# Sitara_IO_Bank_6.net
KiCad netlist of a schematic drawn in Altium Designer
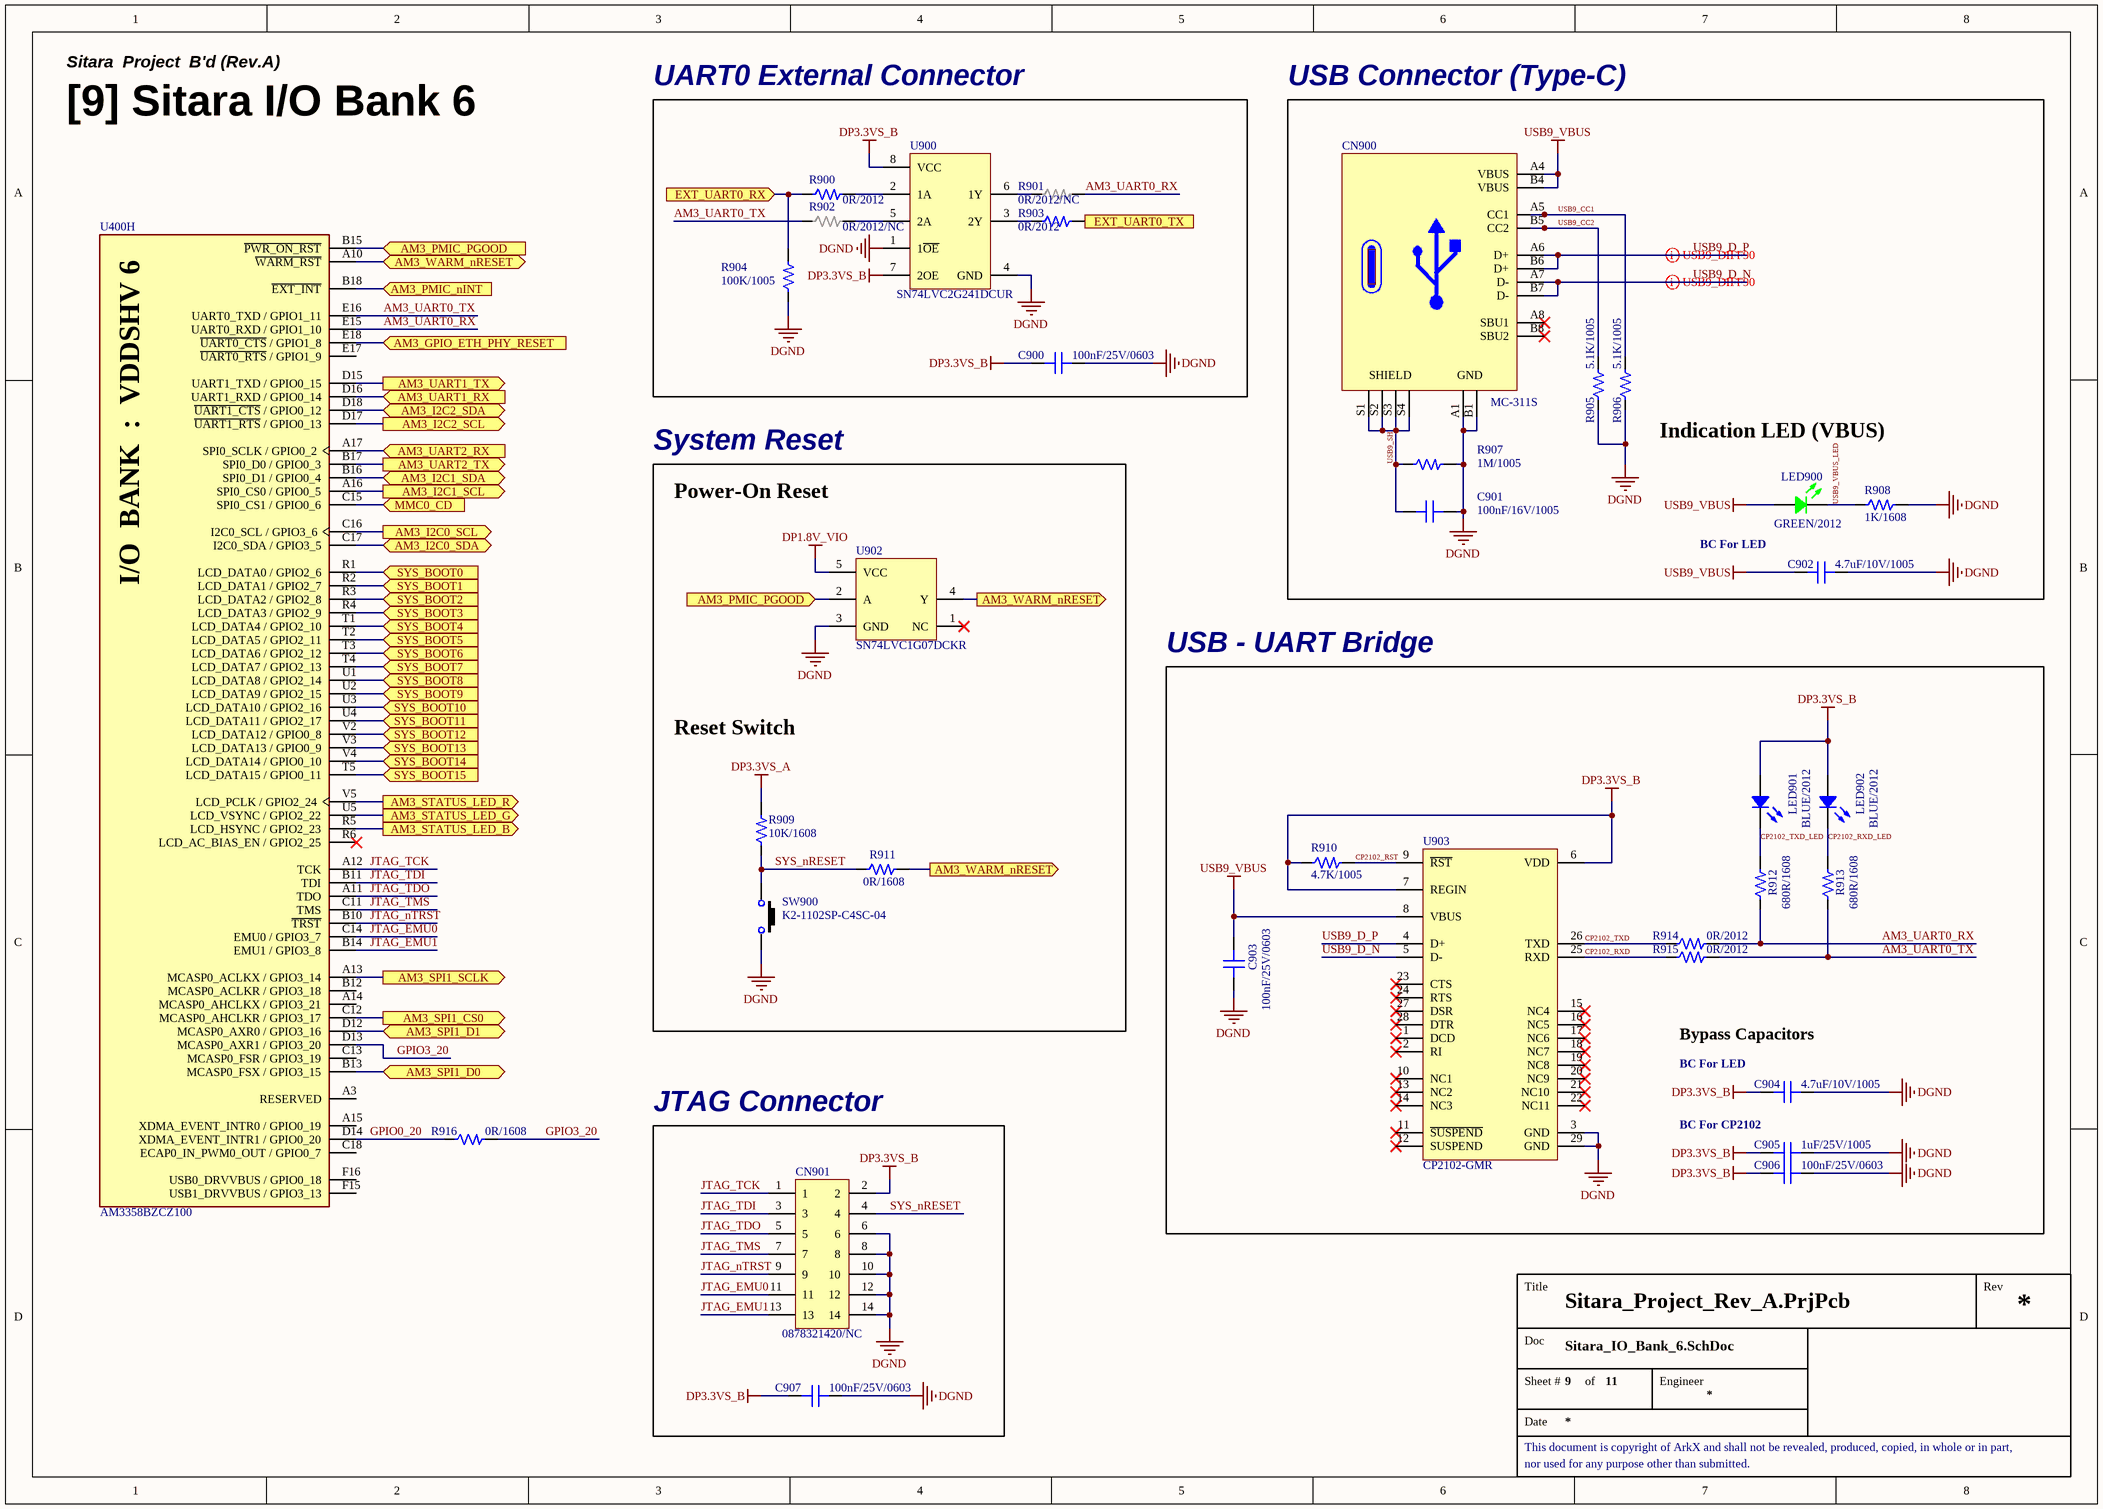
[diagram p0: Sitara_IO_Bank_6.SchDoc]

(export (version "E")
  (design (tool "Eeschema 10.0.6"))
  (components
    (comp (ref "C900")
      (value "100nF/25V/0603")
      (footprint "CAP 0603 (0201_INCH)")
      (description "Ceramic CAP_100nF/25V/0603")
      (fields (field (name "LCSC PART #") "C181047"))
      (libsource (lib "Arkx") (part "CAP_100nF/25V/0603"))
    )
    (comp (ref "C901")
      (value "100nF/16V/1005")
      (footprint "CAP 1005 (0402_INCH)")
      (description "Ceramic CAP_100nF/16V/1005")
      (fields (field (name "LCSC PART #") "C1525"))
      (libsource (lib "Arkx") (part "CAP_100nF/16V/1005"))
    )
    (comp (ref "C902")
      (value "4.7uF/10V/1005")
      (footprint "CAP 1005 (0402_INCH)")
      (description "10V 4.7uF X5R ±20% 0402  Multilayer Ceramic Capacitors MLCC - SMD/SMT ROHS")
      (fields (field (name "LCSC PART #") "C23733"))
      (libsource (lib "Arkx") (part "CAP_4.7uF/10V/1005"))
    )
    (comp (ref "C903")
      (value "100nF/25V/0603")
      (footprint "CAP 0603 (0201_INCH)")
      (description "Ceramic CAP_100nF/25V/0603")
      (fields (field (name "LCSC PART #") "C181047"))
      (libsource (lib "Arkx") (part "CAP_100nF/25V/0603"))
    )
    (comp (ref "C904")
      (value "4.7uF/10V/1005")
      (footprint "CAP 1005 (0402_INCH)")
      (description "10V 4.7uF X5R ±20% 0402  Multilayer Ceramic Capacitors MLCC - SMD/SMT ROHS")
      (fields (field (name "LCSC PART #") "C23733"))
      (libsource (lib "Arkx") (part "CAP_4.7uF/10V/1005"))
    )
    (comp (ref "C905")
      (value "1uF/25V/1005")
      (footprint "CAP 1005 (0402_INCH)")
      (description "Ceramic CAP_1uF/25V/1005")
      (fields (field (name "LCSC PART #") "C52923"))
      (libsource (lib "Arkx") (part "CAP_1uF/25V/1005"))
    )
    (comp (ref "C906")
      (value "100nF/25V/0603")
      (footprint "CAP 0603 (0201_INCH)")
      (description "Ceramic CAP_100nF/25V/0603")
      (fields (field (name "LCSC PART #") "C181047"))
      (libsource (lib "Arkx") (part "CAP_100nF/25V/0603"))
    )
    (comp (ref "C907")
      (value "100nF/25V/0603")
      (footprint "CAP 0603 (0201_INCH)")
      (description "Ceramic CAP_100nF/25V/0603")
      (fields (field (name "LCSC PART #") "C181047"))
      (libsource (lib "Arkx") (part "CAP_100nF/25V/0603"))
    )
    (comp (ref "CN900")
      (value "MC-311S")
      (footprint "CON USB-Type-C (16P)")
      (description "USB 2.0 5A 1 Surface Mount 16 Female -35℃~+75℃ Type-C SMD  USB Connectors ROHS")
      (fields (field (name "LCSC PART #") "C2977718"))
      (libsource (lib "Arkx") (part "CON_USB-Type-C"))
    )
    (comp (ref "CN901")
      (value "0878321420/NC")
      (footprint "CON_NC_BOX_HEADER_DUAL_2x7PIN(2.00MM) (0878321420)")
      (description "CONN HEADER SMD 14POS 2MM")
      (libsource (lib "Arkx") (part "CON_NC_BOX_HEADER_DUAL_2x7PIN(2.00MM)_1"))
    )
    (comp (ref "LED900")
      (value "GREEN/2012")
      (footprint "LED MHT170RGBCT (GREEN)")
      (fields (field (name "LCSC PART #") "C2962094"))
      (libsource (lib "Arkx") (part "LED_MHT170RGBCT(GREEN)"))
    )
    (comp (ref "LED901")
      (value "BLUE/2012")
      (footprint "LED MHT170RGBCT (BLUE)")
      (fields (field (name "LCSC PART #") "C2962094"))
      (libsource (lib "Arkx") (part "LED_MHT170RGBCT(BLUE)"))
    )
    (comp (ref "LED902")
      (value "BLUE/2012")
      (footprint "LED MHT170RGBCT (BLUE)")
      (fields (field (name "LCSC PART #") "C2962094"))
      (libsource (lib "Arkx") (part "LED_MHT170RGBCT(BLUE)"))
    )
    (comp (ref "R900")
      (value "0R/2012")
      (footprint "RES 2012 (0805_inch)")
      (description "RES_0R/2012/0.125W")
      (fields (field (name "LCSC PART #") "C17477"))
      (libsource (lib "Arkx") (part "RES_0R/2012/0.125W"))
    )
    (comp (ref "R901")
      (value "0R/2012/NC")
      (footprint "RES 2012 (0805_INCH)/NC")
      (description "0R/2012/0.125W/NC")
      (libsource (lib "Arkx") (part "RES_NC_0R/2012/0.125W"))
    )
    (comp (ref "R902")
      (value "0R/2012/NC")
      (footprint "RES 2012 (0805_INCH)/NC")
      (description "0R/2012/0.125W/NC")
      (libsource (lib "Arkx") (part "RES_NC_0R/2012/0.125W"))
    )
    (comp (ref "R903")
      (value "0R/2012")
      (footprint "RES 2012 (0805_inch)")
      (description "RES_0R/2012/0.125W")
      (fields (field (name "LCSC PART #") "C17477"))
      (libsource (lib "Arkx") (part "RES_0R/2012/0.125W"))
    )
    (comp (ref "R904")
      (value "100K/1005")
      (footprint "RES 1005 (0402_inch)")
      (description "RES_100K/1005/62.5mW")
      (fields (field (name "LCSC PART #") "C25741"))
      (libsource (lib "Arkx") (part "RES_100K/1005/62.5mW"))
    )
    (comp (ref "R905")
      (value "5.1K/1005")
      (footprint "RES 1005 (0402_inch)")
      (description "RES_5.1K/1005/62.5mW")
      (fields (field (name "LCSC PART #") "C25905"))
      (libsource (lib "Arkx") (part "RES_5.1K/1005/62.5mW"))
    )
    (comp (ref "R906")
      (value "5.1K/1005")
      (footprint "RES 1005 (0402_inch)")
      (description "RES_5.1K/1005/62.5mW")
      (fields (field (name "LCSC PART #") "C25905"))
      (libsource (lib "Arkx") (part "RES_5.1K/1005/62.5mW"))
    )
    (comp (ref "R907")
      (value "1M/1005")
      (footprint "RES 1005 (0402_inch)")
      (description "RES_1M/1005/62.5mW")
      (fields (field (name "LCSC PART #") "C26083"))
      (libsource (lib "Arkx") (part "RES_1M/1005/62.5mW"))
    )
    (comp (ref "R908")
      (value "1K/1608")
      (footprint "RES 1608 (0603_inch)")
      (description "RES_1K/1608/0.1W")
      (fields (field (name "LCSC PART #") "C21190"))
      (libsource (lib "Arkx") (part "RES_1K/1608/0.1W"))
    )
    (comp (ref "R909")
      (value "10K/1608")
      (footprint "RES 1608 (0603_inch)")
      (description "RES_10K/1608/0.1W")
      (fields (field (name "LCSC PART #") "C25804"))
      (libsource (lib "Arkx") (part "RES_10K/1608/0.1W"))
    )
    (comp (ref "R910")
      (value "4.7K/1005")
      (footprint "RES 1005 (0402_inch)")
      (description "RES_4.7K/1005/62.5mW")
      (fields (field (name "LCSC PART #") "C25900"))
      (libsource (lib "Arkx") (part "RES_4.7K/1005/62.5mW"))
    )
    (comp (ref "R911")
      (value "0R/1608")
      (footprint "RES 1608 (0603_inch)")
      (description "RES_0R/1608/0.1W")
      (fields (field (name "LCSC PART #") "C21189"))
      (libsource (lib "Arkx") (part "RES_0R/1608/0.1W"))
    )
    (comp (ref "R912")
      (value "680R/1608")
      (footprint "RES 1608 (0603_inch)")
      (description "RES_680R/1608/0.1W")
      (fields (field (name "LCSC PART #") "C23228"))
      (libsource (lib "Arkx") (part "RES_680R/1608/0.1W"))
    )
    (comp (ref "R913")
      (value "680R/1608")
      (footprint "RES 1608 (0603_inch)")
      (description "RES_680R/1608/0.1W")
      (fields (field (name "LCSC PART #") "C23228"))
      (libsource (lib "Arkx") (part "RES_680R/1608/0.1W"))
    )
    (comp (ref "R914")
      (value "0R/2012")
      (footprint "RES 2012 (0805_inch)")
      (description "RES_0R/2012/0.125W")
      (fields (field (name "LCSC PART #") "C17477"))
      (libsource (lib "Arkx") (part "RES_0R/2012/0.125W"))
    )
    (comp (ref "R915")
      (value "0R/2012")
      (footprint "RES 2012 (0805_inch)")
      (description "RES_0R/2012/0.125W")
      (fields (field (name "LCSC PART #") "C17477"))
      (libsource (lib "Arkx") (part "RES_0R/2012/0.125W"))
    )
    (comp (ref "R916")
      (value "0R/1608")
      (footprint "RES 1608 (0603_inch)")
      (description "RES_0R/1608/0.1W")
      (fields (field (name "LCSC PART #") "C21189"))
      (libsource (lib "Arkx") (part "RES_0R/1608/0.1W"))
    )
    (comp (ref "SW900")
      (value "K2-1102SP-C4SC-04")
      (footprint "SW K2-1102SP-C4SC-04")
      (fields (field (name "LCSC PART #") "C127509"))
      (libsource (lib "Arkx") (part "SW_K2-1102SP-C4SC-04(2P)"))
    )
    (comp (ref "U400")
      (value "AM3358BZCZ100")
      (footprint "IC_SOC_AM3358BZCZ100")
      (description "ARM® Cortex®-A8 Microprocessor IC Sitara™ 1 Core, 32-Bit 1.0GHz 324-NFBGA (15x15)")
      (fields (field (name "LCSC PART #") "C73932"))
      (libsource (lib "Arkx") (part "IC_SOC_AM3358BZCZ100"))
    )
    (comp (ref "U900")
      (value "SN74LVC2G241DCUR")
      (footprint "IC_VSSOP-8")
      (description "Buffer, Non-Inverting 2 Element 1 Bit per Element 3-State Output 8-VSSOP")
      (fields (field (name "LCSC PART #") "C10430"))
      (libsource (lib "Arkx") (part "IC_BUF_SN74LVC2G241DCUR"))
    )
    (comp (ref "U902")
      (value "SN74LVC1G07DCKR")
      (footprint "IC_SC-70-5")
      (description "Buffer, Non-Inverting 1 Element 1 Bit per Element Open Drain Output SC-70-5")
      (fields (field (name "LCSC PART #") "C7830"))
      (libsource (lib "Arkx") (part "IC_BUF_SN74LVC1G07DCKR"))
    )
    (comp (ref "U903")
      (value "CP2102-GMR")
      (footprint "QFN-28 (5x5mm)")
      (description "Transceiver 1Mbps USB 1/1 QFN-28_5x5x05P  USB ICs ROHS")
      (fields (field (name "LCSC PART #") "C6568"))
      (libsource (lib "Arkx") (part "IC_USB_CP2102"))
    )
  )
  (nets
    (net (code "1") (name "/AM3_GPIO_ETH_PHY_RESET") (class "Default")
      (node (ref "U400") (pin "E18") (pinfunction "~{UART0_CTS}_/_GPIO1_8_E18") (pintype "passive"))
    )
    (net (code "2") (name "/AM3_I2C0_SCL") (class "Default")
      (node (ref "U400") (pin "C16") (pinfunction "I2C0_SCL_/_GPIO3_6_C16") (pintype "passive"))
    )
    (net (code "3") (name "/AM3_I2C0_SDA") (class "Default")
      (node (ref "U400") (pin "C17") (pinfunction "I2C0_SDA_/_GPIO3_5_C17") (pintype "passive"))
    )
    (net (code "4") (name "/AM3_I2C1_SCL") (class "Default")
      (node (ref "U400") (pin "A16") (pinfunction "SPI0_CS0_/_GPIO0_5_A16") (pintype "passive"))
    )
    (net (code "5") (name "/AM3_I2C1_SDA") (class "Default")
      (node (ref "U400") (pin "B16") (pinfunction "SPI0_D1_/_GPIO0_4_B16") (pintype "passive"))
    )
    (net (code "6") (name "/AM3_I2C2_SCL") (class "Default")
      (node (ref "U400") (pin "D17") (pinfunction "~{UART1_RTS}_/_GPIO0_13_D17") (pintype "passive"))
    )
    (net (code "7") (name "/AM3_I2C2_SDA") (class "Default")
      (node (ref "U400") (pin "D18") (pinfunction "~{UART1_CTS}_/_GPIO0_12_D18") (pintype "passive"))
    )
    (net (code "8") (name "/AM3_PMIC_PGOOD") (class "Default")
      (node (ref "U400") (pin "B15") (pinfunction "~{PWR_ON_RST}_B15") (pintype "passive"))
      (node (ref "U902") (pin "2") (pinfunction "A_2") (pintype "passive"))
    )
    (net (code "9") (name "/AM3_PMIC_nINT") (class "Default")
      (node (ref "U400") (pin "B18") (pinfunction "~{EXT_INT}_B18") (pintype "passive"))
    )
    (net (code "10") (name "/AM3_SPI1_CS0") (class "Default")
      (node (ref "U400") (pin "C12") (pinfunction "MCASP0_AHCLKR_/_GPIO3_17_C12") (pintype "passive"))
    )
    (net (code "11") (name "/AM3_SPI1_D0") (class "Default")
      (node (ref "U400") (pin "B13") (pinfunction "MCASP0_FSX_/_GPIO3_15_B13") (pintype "passive"))
    )
    (net (code "12") (name "/AM3_SPI1_D1") (class "Default")
      (node (ref "U400") (pin "D12") (pinfunction "MCASP0_AXR0_/_GPIO3_16_D12") (pintype "passive"))
    )
    (net (code "13") (name "/AM3_SPI1_SCLK") (class "Default")
      (node (ref "U400") (pin "A13") (pinfunction "MCASP0_ACLKX_/_GPIO3_14_A13") (pintype "passive"))
    )
    (net (code "14") (name "/AM3_STATUS_LED_B") (class "Default")
      (node (ref "U400") (pin "R5") (pinfunction "LCD_HSYNC_/_GPIO2_23_R5") (pintype "passive"))
    )
    (net (code "15") (name "/AM3_STATUS_LED_G") (class "Default")
      (node (ref "U400") (pin "U5") (pinfunction "LCD_VSYNC_/_GPIO2_22_U5") (pintype "passive"))
    )
    (net (code "16") (name "/AM3_STATUS_LED_R") (class "Default")
      (node (ref "U400") (pin "V5") (pinfunction "LCD_PCLK_/_GPIO2_24_V5") (pintype "passive"))
    )
    (net (code "17") (name "/AM3_UART0_RX") (class "Default")
      (node (ref "R901") (pin "2") (pinfunction "2_2") (pintype "passive"))
      (node (ref "R912") (pin "1") (pinfunction "1_1") (pintype "passive"))
      (node (ref "R914") (pin "2") (pinfunction "2_2") (pintype "passive"))
      (node (ref "U400") (pin "E15") (pinfunction "UART0_RXD_/_GPIO1_10_E15") (pintype "passive"))
    )
    (net (code "18") (name "/AM3_UART0_TX") (class "Default")
      (node (ref "R902") (pin "1") (pinfunction "1_1") (pintype "passive"))
      (node (ref "R913") (pin "1") (pinfunction "1_1") (pintype "passive"))
      (node (ref "R915") (pin "2") (pinfunction "2_2") (pintype "passive"))
      (node (ref "U400") (pin "E16") (pinfunction "UART0_TXD_/_GPIO1_11_E16") (pintype "passive"))
    )
    (net (code "19") (name "/AM3_UART1_RX") (class "Default")
      (node (ref "U400") (pin "D16") (pinfunction "UART1_RXD_/_GPIO0_14_D16") (pintype "passive"))
    )
    (net (code "20") (name "/AM3_UART1_TX") (class "Default")
      (node (ref "U400") (pin "D15") (pinfunction "UART1_TXD_/_GPIO0_15_D15") (pintype "passive"))
    )
    (net (code "21") (name "/AM3_UART2_RX") (class "Default")
      (node (ref "U400") (pin "A17") (pinfunction "SPI0_SCLK_/_GPIO0_2_A17") (pintype "passive"))
    )
    (net (code "22") (name "/AM3_UART2_TX") (class "Default")
      (node (ref "U400") (pin "B17") (pinfunction "SPI0_D0_/_GPIO0_3_B17") (pintype "passive"))
    )
    (net (code "23") (name "/AM3_WARM_nRESET") (class "Default")
      (node (ref "R911") (pin "2") (pinfunction "2_2") (pintype "passive"))
      (node (ref "U400") (pin "A10") (pinfunction "~{WARM_RST}_A10") (pintype "passive"))
      (node (ref "U902") (pin "4") (pinfunction "Y_4") (pintype "passive"))
    )
    (net (code "24") (name "/CP2102_RST") (class "Default")
      (node (ref "R910") (pin "2") (pinfunction "2_2") (pintype "passive"))
      (node (ref "U903") (pin "9") (pinfunction "~{RST}_9") (pintype "passive"))
    )
    (net (code "25") (name "/CP2102_RXD") (class "Default")
      (node (ref "R915") (pin "1") (pinfunction "1_1") (pintype "passive"))
      (node (ref "U903") (pin "25") (pinfunction "RXD_25") (pintype "passive"))
    )
    (net (code "26") (name "/CP2102_RXD_LED") (class "Default")
      (node (ref "LED902") (pin "3") (pinfunction "BLUE_3") (pintype "passive"))
      (node (ref "R913") (pin "2") (pinfunction "2_2") (pintype "passive"))
    )
    (net (code "27") (name "/CP2102_TXD") (class "Default")
      (node (ref "R914") (pin "1") (pinfunction "1_1") (pintype "passive"))
      (node (ref "U903") (pin "26") (pinfunction "TXD_26") (pintype "passive"))
    )
    (net (code "28") (name "/CP2102_TXD_LED") (class "Default")
      (node (ref "LED901") (pin "3") (pinfunction "BLUE_3") (pintype "passive"))
      (node (ref "R912") (pin "2") (pinfunction "2_2") (pintype "passive"))
    )
    (net (code "29") (name "/EXT_UART0_RX") (class "Default")
      (node (ref "R900") (pin "1") (pinfunction "1_1") (pintype "passive"))
      (node (ref "R904") (pin "2") (pinfunction "2_2") (pintype "passive"))
    )
    (net (code "30") (name "/EXT_UART0_TX") (class "Default")
      (node (ref "R903") (pin "2") (pinfunction "2_2") (pintype "passive"))
    )
    (net (code "31") (name "/GPIO0_20") (class "Default")
      (node (ref "R916") (pin "1") (pinfunction "1_1") (pintype "passive"))
      (node (ref "U400") (pin "D14") (pinfunction "XDMA_EVENT_INTR1_/_GPIO0_20_D14") (pintype "passive"))
    )
    (net (code "32") (name "/GPIO3_20") (class "Default")
      (node (ref "R916") (pin "2") (pinfunction "2_2") (pintype "passive"))
      (node (ref "U400") (pin "D13") (pinfunction "MCASP0_AXR1_/_GPIO3_20_D13") (pintype "passive"))
    )
    (net (code "33") (name "/JTAG_EMU0") (class "Default")
      (node (ref "CN901") (pin "11") (pinfunction "11_11") (pintype "passive"))
      (node (ref "U400") (pin "C14") (pinfunction "EMU0_/_GPIO3_7_C14") (pintype "passive"))
    )
    (net (code "34") (name "/JTAG_EMU1") (class "Default")
      (node (ref "CN901") (pin "13") (pinfunction "13_13") (pintype "passive"))
      (node (ref "U400") (pin "B14") (pinfunction "EMU1_/_GPIO3_8_B14") (pintype "passive"))
    )
    (net (code "35") (name "/JTAG_TCK") (class "Default")
      (node (ref "CN901") (pin "1") (pinfunction "1_1") (pintype "passive"))
      (node (ref "U400") (pin "A12") (pinfunction "TCK_A12") (pintype "passive"))
    )
    (net (code "36") (name "/JTAG_TDI") (class "Default")
      (node (ref "CN901") (pin "3") (pinfunction "3_3") (pintype "passive"))
      (node (ref "U400") (pin "B11") (pinfunction "TDI_B11") (pintype "passive"))
    )
    (net (code "37") (name "/JTAG_TDO") (class "Default")
      (node (ref "CN901") (pin "5") (pinfunction "5_5") (pintype "passive"))
      (node (ref "U400") (pin "A11") (pinfunction "TDO_A11") (pintype "passive"))
    )
    (net (code "38") (name "/JTAG_TMS") (class "Default")
      (node (ref "CN901") (pin "7") (pinfunction "7_7") (pintype "passive"))
      (node (ref "U400") (pin "C11") (pinfunction "TMS_C11") (pintype "passive"))
    )
    (net (code "39") (name "/JTAG_nTRST") (class "Default")
      (node (ref "CN901") (pin "9") (pinfunction "9_9") (pintype "passive"))
      (node (ref "U400") (pin "B10") (pinfunction "~{TRST}_B10") (pintype "passive"))
    )
    (net (code "40") (name "/MMC0_CD") (class "Default")
      (node (ref "U400") (pin "C15") (pinfunction "SPI0_CS1_/_GPIO0_6_C15") (pintype "passive"))
    )
    (net (code "41") (name "/SYS_BOOT0") (class "Default")
      (node (ref "U400") (pin "R1") (pinfunction "LCD_DATA0_/_GPIO2_6_R1") (pintype "passive"))
    )
    (net (code "42") (name "/SYS_BOOT1") (class "Default")
      (node (ref "U400") (pin "R2") (pinfunction "LCD_DATA1_/_GPIO2_7_R2") (pintype "passive"))
    )
    (net (code "43") (name "/SYS_BOOT2") (class "Default")
      (node (ref "U400") (pin "R3") (pinfunction "LCD_DATA2_/_GPIO2_8_R3") (pintype "passive"))
    )
    (net (code "44") (name "/SYS_BOOT3") (class "Default")
      (node (ref "U400") (pin "R4") (pinfunction "LCD_DATA3_/_GPIO2_9_R4") (pintype "passive"))
    )
    (net (code "45") (name "/SYS_BOOT4") (class "Default")
      (node (ref "U400") (pin "T1") (pinfunction "LCD_DATA4_/_GPIO2_10_T1") (pintype "passive"))
    )
    (net (code "46") (name "/SYS_BOOT5") (class "Default")
      (node (ref "U400") (pin "T2") (pinfunction "LCD_DATA5_/_GPIO2_11_T2") (pintype "passive"))
    )
    (net (code "47") (name "/SYS_BOOT6") (class "Default")
      (node (ref "U400") (pin "T3") (pinfunction "LCD_DATA6_/_GPIO2_12_T3") (pintype "passive"))
    )
    (net (code "48") (name "/SYS_BOOT7") (class "Default")
      (node (ref "U400") (pin "T4") (pinfunction "LCD_DATA7_/_GPIO2_13_T4") (pintype "passive"))
    )
    (net (code "49") (name "/SYS_BOOT8") (class "Default")
      (node (ref "U400") (pin "U1") (pinfunction "LCD_DATA8_/_GPIO2_14_U1") (pintype "passive"))
    )
    (net (code "50") (name "/SYS_BOOT9") (class "Default")
      (node (ref "U400") (pin "U2") (pinfunction "LCD_DATA9_/_GPIO2_15_U2") (pintype "passive"))
    )
    (net (code "51") (name "/SYS_BOOT10") (class "Default")
      (node (ref "U400") (pin "U3") (pinfunction "LCD_DATA10_/_GPIO2_16_U3") (pintype "passive"))
    )
    (net (code "52") (name "/SYS_BOOT11") (class "Default")
      (node (ref "U400") (pin "U4") (pinfunction "LCD_DATA11_/_GPIO2_17_U4") (pintype "passive"))
    )
    (net (code "53") (name "/SYS_BOOT12") (class "Default")
      (node (ref "U400") (pin "V2") (pinfunction "LCD_DATA12_/_GPIO0_8_V2") (pintype "passive"))
    )
    (net (code "54") (name "/SYS_BOOT13") (class "Default")
      (node (ref "U400") (pin "V3") (pinfunction "LCD_DATA13_/_GPIO0_9_V3") (pintype "passive"))
    )
    (net (code "55") (name "/SYS_BOOT14") (class "Default")
      (node (ref "U400") (pin "V4") (pinfunction "LCD_DATA14_/_GPIO0_10_V4") (pintype "passive"))
    )
    (net (code "56") (name "/SYS_BOOT15") (class "Default")
      (node (ref "U400") (pin "T5") (pinfunction "LCD_DATA15_/_GPIO0_11_T5") (pintype "passive"))
    )
    (net (code "57") (name "/SYS_nRESET") (class "Default")
      (node (ref "CN901") (pin "4") (pinfunction "4_4") (pintype "passive"))
      (node (ref "R909") (pin "1") (pinfunction "1_1") (pintype "passive"))
      (node (ref "R911") (pin "1") (pinfunction "1_1") (pintype "passive"))
      (node (ref "SW900") (pin "1") (pinfunction "1_1") (pintype "passive"))
    )
    (net (code "58") (name "/USB9_CC1") (class "Default")
      (node (ref "CN900") (pin "A5") (pinfunction "CC1_A5") (pintype "passive"))
      (node (ref "R906") (pin "2") (pinfunction "2_2") (pintype "passive"))
    )
    (net (code "59") (name "/USB9_CC2") (class "Default")
      (node (ref "CN900") (pin "B5") (pinfunction "CC2_B5") (pintype "passive"))
      (node (ref "R905") (pin "2") (pinfunction "2_2") (pintype "passive"))
    )
    (net (code "60") (name "/USB9_D_N") (class "Default")
      (node (ref "CN900") (pin "A7") (pinfunction "D-_A7") (pintype "passive"))
      (node (ref "CN900") (pin "B7") (pinfunction "D-_B7") (pintype "passive"))
      (node (ref "U903") (pin "5") (pinfunction "D-_5") (pintype "passive"))
    )
    (net (code "61") (name "/USB9_D_P") (class "Default")
      (node (ref "CN900") (pin "A6") (pinfunction "D+_A6") (pintype "passive"))
      (node (ref "CN900") (pin "B6") (pinfunction "D+_B6") (pintype "passive"))
      (node (ref "U903") (pin "4") (pinfunction "D+_4") (pintype "passive"))
    )
    (net (code "62") (name "/USB9_SH") (class "Default")
      (node (ref "C901") (pin "2") (pinfunction "2_2") (pintype "passive"))
      (node (ref "CN900") (pin "S1") (pinfunction "SHIELD_S1") (pintype "passive"))
      (node (ref "CN900") (pin "S2") (pinfunction "SHIELD_S2") (pintype "passive"))
      (node (ref "CN900") (pin "S3") (pinfunction "SHIELD_S3") (pintype "passive"))
      (node (ref "CN900") (pin "S4") (pinfunction "SHIELD_S4") (pintype "passive"))
      (node (ref "R907") (pin "1") (pinfunction "1_1") (pintype "passive"))
    )
    (net (code "63") (name "/USB9_VBUS_LED") (class "Default")
      (node (ref "LED900") (pin "2") (pinfunction "GREEN_2") (pintype "passive"))
      (node (ref "R908") (pin "1") (pinfunction "1_1") (pintype "passive"))
    )
    (net (code "64") (name "DGND") (class "Default")
      (node (ref "C900") (pin "1") (pinfunction "1_1") (pintype "passive"))
      (node (ref "C901") (pin "1") (pinfunction "1_1") (pintype "passive"))
      (node (ref "C902") (pin "1") (pinfunction "1_1") (pintype "passive"))
      (node (ref "C903") (pin "2") (pinfunction "2_2") (pintype "passive"))
      (node (ref "C904") (pin "1") (pinfunction "1_1") (pintype "passive"))
      (node (ref "C905") (pin "2") (pinfunction "2_2") (pintype "passive"))
      (node (ref "C906") (pin "1") (pinfunction "1_1") (pintype "passive"))
      (node (ref "C907") (pin "1") (pinfunction "1_1") (pintype "passive"))
      (node (ref "CN900") (pin "A1") (pinfunction "GND_A1") (pintype "passive"))
      (node (ref "CN900") (pin "B1") (pinfunction "GND_B1") (pintype "passive"))
      (node (ref "CN901") (pin "10") (pinfunction "10_10") (pintype "passive"))
      (node (ref "CN901") (pin "12") (pinfunction "12_12") (pintype "passive"))
      (node (ref "CN901") (pin "14") (pinfunction "14_14") (pintype "passive"))
      (node (ref "CN901") (pin "6") (pinfunction "6_6") (pintype "passive"))
      (node (ref "CN901") (pin "8") (pinfunction "8_8") (pintype "passive"))
      (node (ref "R904") (pin "1") (pinfunction "1_1") (pintype "passive"))
      (node (ref "R905") (pin "1") (pinfunction "1_1") (pintype "passive"))
      (node (ref "R906") (pin "1") (pinfunction "1_1") (pintype "passive"))
      (node (ref "R907") (pin "2") (pinfunction "2_2") (pintype "passive"))
      (node (ref "R908") (pin "2") (pinfunction "2_2") (pintype "passive"))
      (node (ref "SW900") (pin "3") (pinfunction "3_3") (pintype "passive"))
      (node (ref "U900") (pin "1") (pinfunction "1~{OE}_1") (pintype "passive"))
      (node (ref "U900") (pin "4") (pinfunction "GND_4") (pintype "passive"))
      (node (ref "U902") (pin "3") (pinfunction "GND_3") (pintype "passive"))
      (node (ref "U903") (pin "29") (pinfunction "GND_29") (pintype "passive"))
      (node (ref "U903") (pin "3") (pinfunction "GND_3") (pintype "passive"))
    )
    (net (code "65") (name "DP1.8V_VIO") (class "Default")
      (node (ref "U902") (pin "5") (pinfunction "VCC_5") (pintype "passive"))
    )
    (net (code "66") (name "DP3.3VS_A") (class "Default")
      (node (ref "R909") (pin "2") (pinfunction "2_2") (pintype "passive"))
    )
    (net (code "67") (name "DP3.3VS_B") (class "Default")
      (node (ref "C900") (pin "2") (pinfunction "2_2") (pintype "passive"))
      (node (ref "C904") (pin "2") (pinfunction "2_2") (pintype "passive"))
      (node (ref "C905") (pin "1") (pinfunction "1_1") (pintype "passive"))
      (node (ref "C906") (pin "2") (pinfunction "2_2") (pintype "passive"))
      (node (ref "C907") (pin "2") (pinfunction "2_2") (pintype "passive"))
      (node (ref "CN901") (pin "2") (pinfunction "2_2") (pintype "passive"))
      (node (ref "LED901") (pin "4") (pinfunction "Common_Anode_4") (pintype "passive"))
      (node (ref "LED902") (pin "4") (pinfunction "Common_Anode_4") (pintype "passive"))
      (node (ref "R910") (pin "1") (pinfunction "1_1") (pintype "passive"))
      (node (ref "U900") (pin "7") (pinfunction "2OE_7") (pintype "passive"))
      (node (ref "U900") (pin "8") (pinfunction "VCC_8") (pintype "passive"))
      (node (ref "U903") (pin "6") (pinfunction "VDD_6") (pintype "passive"))
      (node (ref "U903") (pin "7") (pinfunction "REGIN_7") (pintype "passive"))
    )
    (net (code "68") (name "Net-(U900-1A)") (class "Default")
      (node (ref "R900") (pin "2") (pinfunction "2_2") (pintype "passive"))
      (node (ref "U900") (pin "2") (pinfunction "1A_2") (pintype "passive"))
    )
    (net (code "69") (name "Net-(U900-1Y)") (class "Default")
      (node (ref "R901") (pin "1") (pinfunction "1_1") (pintype "passive"))
      (node (ref "U900") (pin "6") (pinfunction "1Y_6") (pintype "passive"))
    )
    (net (code "70") (name "Net-(U900-2A)") (class "Default")
      (node (ref "R902") (pin "2") (pinfunction "2_2") (pintype "passive"))
      (node (ref "U900") (pin "5") (pinfunction "2A_5") (pintype "passive"))
    )
    (net (code "71") (name "Net-(U900-2Y)") (class "Default")
      (node (ref "R903") (pin "1") (pinfunction "1_1") (pintype "passive"))
      (node (ref "U900") (pin "3") (pinfunction "2Y_3") (pintype "passive"))
    )
    (net (code "72") (name "USB9_VBUS") (class "Default")
      (node (ref "C902") (pin "2") (pinfunction "2_2") (pintype "passive"))
      (node (ref "C903") (pin "1") (pinfunction "1_1") (pintype "passive"))
      (node (ref "CN900") (pin "A4") (pinfunction "VBUS_A4") (pintype "passive"))
      (node (ref "CN900") (pin "B4") (pinfunction "VBUS_B4") (pintype "passive"))
      (node (ref "LED900") (pin "4") (pinfunction "Common_Anode_4") (pintype "passive"))
      (node (ref "U903") (pin "8") (pinfunction "VBUS_8") (pintype "passive"))
    )
    (net (code "73") (name "unconnected-(CN900-SBU1-PadA8)") (class "Default")
      (node (ref "CN900") (pin "A8") (pinfunction "SBU1_A8") (pintype "passive+no_connect"))
    )
    (net (code "74") (name "unconnected-(CN900-SBU2-PadB8)") (class "Default")
      (node (ref "CN900") (pin "B8") (pinfunction "SBU2_B8") (pintype "passive+no_connect"))
    )
    (net (code "75") (name "unconnected-(U400H-ECAP0_IN_PWM0_OUT_{slash}_GPIO0_7-PadC18)") (class "Default")
      (node (ref "U400") (pin "C18") (pinfunction "ECAP0_IN_PWM0_OUT_/_GPIO0_7_C18") (pintype "passive"))
    )
    (net (code "76") (name "unconnected-(U400H-LCD_AC_BIAS_EN_{slash}_GPIO2_25-PadR6)") (class "Default")
      (node (ref "U400") (pin "R6") (pinfunction "LCD_AC_BIAS_EN_/_GPIO2_25_R6") (pintype "passive+no_connect"))
    )
    (net (code "77") (name "unconnected-(U400H-MCASP0_ACLKR_{slash}_GPIO3_18-PadB12)") (class "Default")
      (node (ref "U400") (pin "B12") (pinfunction "MCASP0_ACLKR_/_GPIO3_18_B12") (pintype "passive"))
    )
    (net (code "78") (name "unconnected-(U400H-MCASP0_AHCLKX_{slash}_GPIO3_21-PadA14)") (class "Default")
      (node (ref "U400") (pin "A14") (pinfunction "MCASP0_AHCLKX_/_GPIO3_21_A14") (pintype "passive"))
    )
    (net (code "79") (name "unconnected-(U400H-MCASP0_FSR_{slash}_GPIO3_19-PadC13)") (class "Default")
      (node (ref "U400") (pin "C13") (pinfunction "MCASP0_FSR_/_GPIO3_19_C13") (pintype "passive"))
    )
    (net (code "80") (name "unconnected-(U400H-RESERVED-PadA3)") (class "Default")
      (node (ref "U400") (pin "A3") (pinfunction "RESERVED_A3") (pintype "passive"))
    )
    (net (code "81") (name "unconnected-(U400H-USB0_DRVVBUS_{slash}_GPIO0_18-PadF16)") (class "Default")
      (node (ref "U400") (pin "F16") (pinfunction "USB0_DRVVBUS_/_GPIO0_18_F16") (pintype "passive"))
    )
    (net (code "82") (name "unconnected-(U400H-USB1_DRVVBUS_{slash}_GPIO3_13-PadF15)") (class "Default")
      (node (ref "U400") (pin "F15") (pinfunction "USB1_DRVVBUS_/_GPIO3_13_F15") (pintype "passive"))
    )
    (net (code "83") (name "unconnected-(U400H-XDMA_EVENT_INTR0_{slash}_GPIO0_19-PadA15)") (class "Default")
      (node (ref "U400") (pin "A15") (pinfunction "XDMA_EVENT_INTR0_/_GPIO0_19_A15") (pintype "passive"))
    )
    (net (code "84") (name "unconnected-(U400H-~{UART0_RTS}_{slash}_GPIO1_9-PadE17)") (class "Default")
      (node (ref "U400") (pin "E17") (pinfunction "~{UART0_RTS}_/_GPIO1_9_E17") (pintype "passive"))
    )
    (net (code "85") (name "unconnected-(U902-NC-Pad1)") (class "Default")
      (node (ref "U902") (pin "1") (pinfunction "NC_1") (pintype "passive+no_connect"))
    )
    (net (code "86") (name "unconnected-(U903-CTS-Pad23)") (class "Default")
      (node (ref "U903") (pin "23") (pinfunction "CTS_23") (pintype "passive+no_connect"))
    )
    (net (code "87") (name "unconnected-(U903-DCD-Pad1)") (class "Default")
      (node (ref "U903") (pin "1") (pinfunction "DCD_1") (pintype "passive+no_connect"))
    )
    (net (code "88") (name "unconnected-(U903-DSR-Pad27)") (class "Default")
      (node (ref "U903") (pin "27") (pinfunction "DSR_27") (pintype "passive+no_connect"))
    )
    (net (code "89") (name "unconnected-(U903-DTR-Pad28)") (class "Default")
      (node (ref "U903") (pin "28") (pinfunction "DTR_28") (pintype "passive+no_connect"))
    )
    (net (code "90") (name "unconnected-(U903-NC1-Pad10)") (class "Default")
      (node (ref "U903") (pin "10") (pinfunction "NC1_10") (pintype "passive+no_connect"))
    )
    (net (code "91") (name "unconnected-(U903-NC2-Pad13)") (class "Default")
      (node (ref "U903") (pin "13") (pinfunction "NC2_13") (pintype "passive+no_connect"))
    )
    (net (code "92") (name "unconnected-(U903-NC3-Pad14)") (class "Default")
      (node (ref "U903") (pin "14") (pinfunction "NC3_14") (pintype "passive+no_connect"))
    )
    (net (code "93") (name "unconnected-(U903-NC4-Pad15)") (class "Default")
      (node (ref "U903") (pin "15") (pinfunction "NC4_15") (pintype "passive+no_connect"))
    )
    (net (code "94") (name "unconnected-(U903-NC5-Pad16)") (class "Default")
      (node (ref "U903") (pin "16") (pinfunction "NC5_16") (pintype "passive+no_connect"))
    )
    (net (code "95") (name "unconnected-(U903-NC6-Pad17)") (class "Default")
      (node (ref "U903") (pin "17") (pinfunction "NC6_17") (pintype "passive+no_connect"))
    )
    (net (code "96") (name "unconnected-(U903-NC7-Pad18)") (class "Default")
      (node (ref "U903") (pin "18") (pinfunction "NC7_18") (pintype "passive+no_connect"))
    )
    (net (code "97") (name "unconnected-(U903-NC8-Pad19)") (class "Default")
      (node (ref "U903") (pin "19") (pinfunction "NC8_19") (pintype "passive+no_connect"))
    )
    (net (code "98") (name "unconnected-(U903-NC9-Pad20)") (class "Default")
      (node (ref "U903") (pin "20") (pinfunction "NC9_20") (pintype "passive+no_connect"))
    )
    (net (code "99") (name "unconnected-(U903-NC10-Pad21)") (class "Default")
      (node (ref "U903") (pin "21") (pinfunction "NC10_21") (pintype "passive+no_connect"))
    )
    (net (code "100") (name "unconnected-(U903-NC11-Pad22)") (class "Default")
      (node (ref "U903") (pin "22") (pinfunction "NC11_22") (pintype "passive+no_connect"))
    )
    (net (code "101") (name "unconnected-(U903-RI-Pad2)") (class "Default")
      (node (ref "U903") (pin "2") (pinfunction "RI_2") (pintype "passive+no_connect"))
    )
    (net (code "102") (name "unconnected-(U903-RTS-Pad24)") (class "Default")
      (node (ref "U903") (pin "24") (pinfunction "RTS_24") (pintype "passive+no_connect"))
    )
    (net (code "103") (name "unconnected-(U903-SUSPEND-Pad12)") (class "Default")
      (node (ref "U903") (pin "12") (pinfunction "SUSPEND_12") (pintype "passive+no_connect"))
    )
    (net (code "104") (name "unconnected-(U903-~{SUSPEND}-Pad11)") (class "Default")
      (node (ref "U903") (pin "11") (pinfunction "~{SUSPEND}_11") (pintype "passive+no_connect"))
    )
  )
)
